# 08_-_MCU.net
KiCad netlist of a schematic drawn in Altium Designer
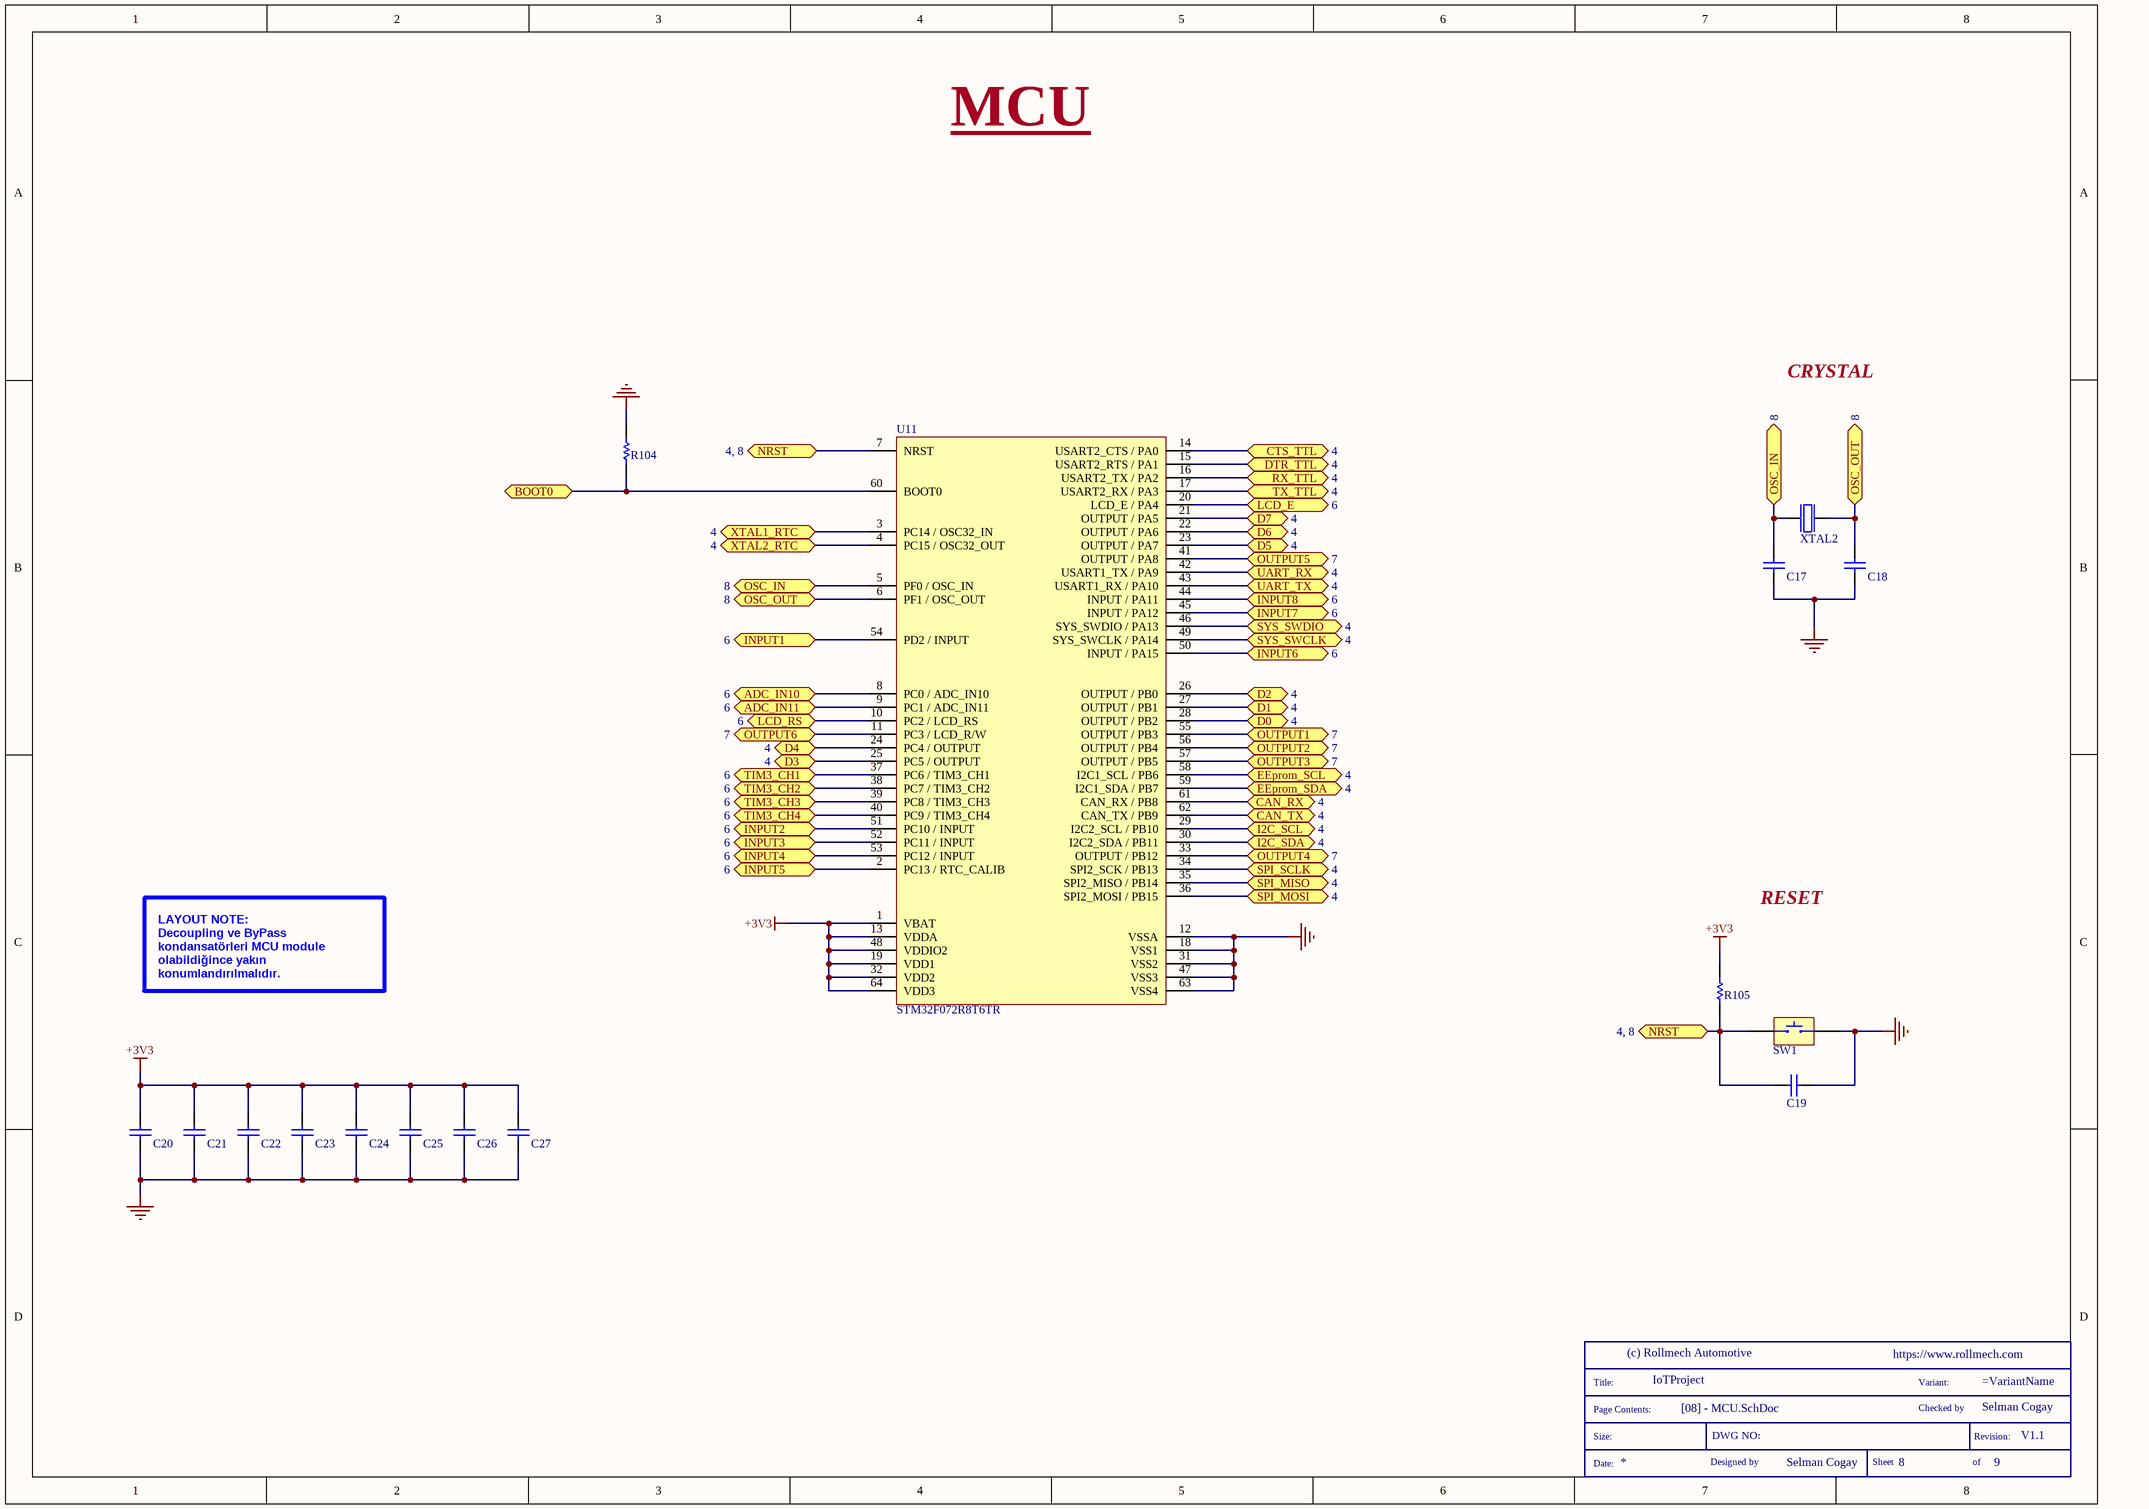
[diagram p0: [08] - MCU.SchDoc]

(export (version "E")
  (design (tool "Eeschema 10.0.6"))
  (components
    (comp (ref "C17")
      (value "22pF 100V")
      (footprint "CAP_CER_0603")
      (description "CAP CER 22PF 100V C0G/NP0 0603")
      (libsource (lib "Rollmech_Altium") (part "GCM1885C2A220FA16D"))
    )
    (comp (ref "C18")
      (value "22pF 100V")
      (footprint "CAP_CER_0603")
      (description "CAP CER 22PF 100V C0G/NP0 0603")
      (libsource (lib "Rollmech_Altium") (part "GCM1885C2A220FA16D"))
    )
    (comp (ref "C19")
      (value "100nF 35V")
      (footprint "CAP_CER_0603")
      (description "CAP CER 100nf 35V X5R 0603")
      (libsource (lib "Rollmech_Altium") (part "GMK107BJ104KAHT"))
    )
    (comp (ref "C20")
      (value "100nF 35V")
      (footprint "CAP_CER_0603")
      (description "CAP CER 100nf 35V X5R 0603")
      (libsource (lib "Rollmech_Altium") (part "GMK107BJ104KAHT"))
    )
    (comp (ref "C21")
      (value "100nF 35V")
      (footprint "CAP_CER_0603")
      (description "CAP CER 100nf 35V X5R 0603")
      (libsource (lib "Rollmech_Altium") (part "GMK107BJ104KAHT"))
    )
    (comp (ref "C22")
      (value "100nF 35V")
      (footprint "CAP_CER_0603")
      (description "CAP CER 100nf 35V X5R 0603")
      (libsource (lib "Rollmech_Altium") (part "GMK107BJ104KAHT"))
    )
    (comp (ref "C23")
      (value "100nF 35V")
      (footprint "CAP_CER_0603")
      (description "CAP CER 100nf 35V X5R 0603")
      (libsource (lib "Rollmech_Altium") (part "GMK107BJ104KAHT"))
    )
    (comp (ref "C24")
      (value "1uF 35V")
      (footprint "C0603")
      (description "CAP CER 1UF 35V")
      (libsource (lib "Rollmech_Altium") (part "CGA3E3X5R1V105K080AB"))
    )
    (comp (ref "C25")
      (value "10nF 100V")
      (footprint "CAP_CER_0805")
      (description "CAP CER 10nF 100V")
      (libsource (lib "Rollmech_Altium") (part "CL21B103KC6WPNC"))
    )
    (comp (ref "C26")
      (value "4.7uF 35V")
      (footprint "CAP_CER_0805")
      (description "CAP CER 100nf 35V X5R 0603")
      (libsource (lib "Rollmech_Altium") (part "GRT21BC8YA475KE13L"))
    )
    (comp (ref "C27")
      (value "4.7uF 35V")
      (footprint "CAP_CER_0805")
      (description "CAP CER 100nf 35V X5R 0603")
      (libsource (lib "Rollmech_Altium") (part "GRT21BC8YA475KE13L"))
    )
    (comp (ref "R104")
      (value "5.6k 1/8W")
      (footprint "RES_0805")
      (description "RES SMD 5.6K OHM 1% 1/8W 0805")
      (libsource (lib "Rollmech_Altium") (part "ERJ-6ENF5601V"))
    )
    (comp (ref "R105")
      (value "5.6k 1/8W")
      (footprint "RES_0805")
      (description "RES SMD 5.6K OHM 1% 1/8W 0805")
      (libsource (lib "Rollmech_Altium") (part "ERJ-6ENF5601V"))
    )
    (comp (ref "SW1")
      (value "TAC SW")
      (footprint "TAC-SW")
      (description "SWITCH TACTILE SPST-NO 0.05A 24V")
      (libsource (lib "Rollmech_Altium") (part "FSMSMTR"))
    )
    (comp (ref "U11")
      (value "STM32F072R8T6TR")
      (footprint "LQFP64")
      (description "IC MCU 32BIT 64KB FLASH 64LQFP")
      (libsource (lib "Rollmech_Altium") (part "STM32F072R8T6TR"))
    )
    (comp (ref "XTAL2")
      (value "8.000MHZ")
      (footprint "XTAL_4SMD")
      (description "CRYSTAL 8.000MHZ")
      (libsource (lib "Rollmech_Altium") (part "ECS-80-18-20BQ-DS"))
    )
  )
  (nets
    (net (code "1") (name "+3V3") (class "Default")
      (node (ref "C20") (pin "2") (pinfunction "2_2") (pintype "passive"))
      (node (ref "C21") (pin "2") (pinfunction "2_2") (pintype "passive"))
      (node (ref "C22") (pin "2") (pinfunction "2_2") (pintype "passive"))
      (node (ref "C23") (pin "2") (pinfunction "2_2") (pintype "passive"))
      (node (ref "C24") (pin "2") (pinfunction "2_2") (pintype "passive"))
      (node (ref "C25") (pin "2") (pinfunction "2_2") (pintype "passive"))
      (node (ref "C26") (pin "2") (pinfunction "2_2") (pintype "passive"))
      (node (ref "C27") (pin "2") (pinfunction "2_2") (pintype "passive"))
      (node (ref "R105") (pin "2") (pinfunction "2_2") (pintype "passive"))
      (node (ref "U11") (pin "1") (pinfunction "VBAT_1") (pintype "passive"))
      (node (ref "U11") (pin "13") (pinfunction "VDDA_13") (pintype "passive"))
      (node (ref "U11") (pin "19") (pinfunction "VDD1_19") (pintype "passive"))
      (node (ref "U11") (pin "32") (pinfunction "VDD2_32") (pintype "passive"))
      (node (ref "U11") (pin "48") (pinfunction "VDDIO2_48") (pintype "passive"))
      (node (ref "U11") (pin "64") (pinfunction "VDD3_64") (pintype "passive"))
    )
    (net (code "2") (name "/ADC_IN10") (class "Default")
      (node (ref "U11") (pin "8") (pinfunction "PC0_/_ADC_IN10_8") (pintype "passive"))
    )
    (net (code "3") (name "/ADC_IN11") (class "Default")
      (node (ref "U11") (pin "9") (pinfunction "PC1_/_ADC_IN11_9") (pintype "passive"))
    )
    (net (code "4") (name "/BOOT0") (class "Default")
      (node (ref "R104") (pin "1") (pinfunction "1_1") (pintype "passive"))
      (node (ref "U11") (pin "60") (pinfunction "BOOT0_60") (pintype "passive"))
    )
    (net (code "5") (name "/CAN_RX") (class "Default")
      (node (ref "U11") (pin "61") (pinfunction "CAN_RX_/_PB8_61") (pintype "passive"))
    )
    (net (code "6") (name "/CAN_TX") (class "Default")
      (node (ref "U11") (pin "62") (pinfunction "CAN_TX_/_PB9_62") (pintype "passive"))
    )
    (net (code "7") (name "/CTS_TTL") (class "Default")
      (node (ref "U11") (pin "14") (pinfunction "USART2_CTS_/_PA0_14") (pintype "passive"))
    )
    (net (code "8") (name "/D0") (class "Default")
      (node (ref "U11") (pin "28") (pinfunction "OUTPUT_/_PB2_28") (pintype "passive"))
    )
    (net (code "9") (name "/D1") (class "Default")
      (node (ref "U11") (pin "27") (pinfunction "OUTPUT_/_PB1_27") (pintype "passive"))
    )
    (net (code "10") (name "/D2") (class "Default")
      (node (ref "U11") (pin "26") (pinfunction "OUTPUT_/_PB0_26") (pintype "passive"))
    )
    (net (code "11") (name "/D3") (class "Default")
      (node (ref "U11") (pin "25") (pinfunction "PC5_/_OUTPUT_25") (pintype "passive"))
    )
    (net (code "12") (name "/D4") (class "Default")
      (node (ref "U11") (pin "24") (pinfunction "PC4_/_OUTPUT_24") (pintype "passive"))
    )
    (net (code "13") (name "/D5") (class "Default")
      (node (ref "U11") (pin "23") (pinfunction "OUTPUT_/_PA7_23") (pintype "passive"))
    )
    (net (code "14") (name "/D6") (class "Default")
      (node (ref "U11") (pin "22") (pinfunction "OUTPUT_/_PA6_22") (pintype "passive"))
    )
    (net (code "15") (name "/D7") (class "Default")
      (node (ref "U11") (pin "21") (pinfunction "OUTPUT_/_PA5_21") (pintype "passive"))
    )
    (net (code "16") (name "/DTR_TTL") (class "Default")
      (node (ref "U11") (pin "15") (pinfunction "USART2_RTS_/_PA1_15") (pintype "passive"))
    )
    (net (code "17") (name "/EEprom_SCL") (class "Default")
      (node (ref "U11") (pin "58") (pinfunction "I2C1_SCL_/_PB6_58") (pintype "passive"))
    )
    (net (code "18") (name "/EEprom_SDA") (class "Default")
      (node (ref "U11") (pin "59") (pinfunction "I2C1_SDA_/_PB7_59") (pintype "passive"))
    )
    (net (code "19") (name "/I2C_SCL") (class "Default")
      (node (ref "U11") (pin "29") (pinfunction "I2C2_SCL_/_PB10_29") (pintype "passive"))
    )
    (net (code "20") (name "/I2C_SDA") (class "Default")
      (node (ref "U11") (pin "30") (pinfunction "I2C2_SDA_/_PB11_30") (pintype "passive"))
    )
    (net (code "21") (name "/INPUT1") (class "Default")
      (node (ref "U11") (pin "54") (pinfunction "PD2_/_INPUT_54") (pintype "passive"))
    )
    (net (code "22") (name "/INPUT2") (class "Default")
      (node (ref "U11") (pin "51") (pinfunction "PC10_/_INPUT_51") (pintype "passive"))
    )
    (net (code "23") (name "/INPUT3") (class "Default")
      (node (ref "U11") (pin "52") (pinfunction "PC11_/_INPUT_52") (pintype "passive"))
    )
    (net (code "24") (name "/INPUT4") (class "Default")
      (node (ref "U11") (pin "53") (pinfunction "PC12_/_INPUT_53") (pintype "passive"))
    )
    (net (code "25") (name "/INPUT5") (class "Default")
      (node (ref "U11") (pin "2") (pinfunction "PC13_/_RTC_CALIB_2") (pintype "passive"))
    )
    (net (code "26") (name "/INPUT6") (class "Default")
      (node (ref "U11") (pin "50") (pinfunction "INPUT_/_PA15_50") (pintype "passive"))
    )
    (net (code "27") (name "/INPUT7") (class "Default")
      (node (ref "U11") (pin "45") (pinfunction "INPUT_/_PA12_45") (pintype "passive"))
    )
    (net (code "28") (name "/INPUT8") (class "Default")
      (node (ref "U11") (pin "44") (pinfunction "INPUT_/_PA11_44") (pintype "passive"))
    )
    (net (code "29") (name "/LCD_E") (class "Default")
      (node (ref "U11") (pin "20") (pinfunction "LCD_E_/_PA4_20") (pintype "passive"))
    )
    (net (code "30") (name "/LCD_RS") (class "Default")
      (node (ref "U11") (pin "10") (pinfunction "PC2_/_LCD_RS_10") (pintype "passive"))
    )
    (net (code "31") (name "/NRST") (class "Default")
      (node (ref "C19") (pin "1") (pinfunction "1_1") (pintype "passive"))
      (node (ref "R105") (pin "1") (pinfunction "1_1") (pintype "passive"))
      (node (ref "SW1") (pin "1") (pinfunction "1_1") (pintype "passive"))
      (node (ref "U11") (pin "7") (pinfunction "NRST_7") (pintype "passive"))
    )
    (net (code "32") (name "/OSC_IN") (class "Default")
      (node (ref "C17") (pin "2") (pinfunction "2_2") (pintype "passive"))
      (node (ref "U11") (pin "5") (pinfunction "PF0_/_OSC_IN_5") (pintype "passive"))
      (node (ref "XTAL2") (pin "3") (pinfunction "3_3") (pintype "passive"))
    )
    (net (code "33") (name "/OSC_OUT") (class "Default")
      (node (ref "C18") (pin "2") (pinfunction "2_2") (pintype "passive"))
      (node (ref "U11") (pin "6") (pinfunction "PF1_/_OSC_OUT_6") (pintype "passive"))
      (node (ref "XTAL2") (pin "1") (pinfunction "1_1") (pintype "passive"))
    )
    (net (code "34") (name "/OUTPUT1") (class "Default")
      (node (ref "U11") (pin "55") (pinfunction "OUTPUT_/_PB3_55") (pintype "passive"))
    )
    (net (code "35") (name "/OUTPUT2") (class "Default")
      (node (ref "U11") (pin "56") (pinfunction "OUTPUT_/_PB4_56") (pintype "passive"))
    )
    (net (code "36") (name "/OUTPUT3") (class "Default")
      (node (ref "U11") (pin "57") (pinfunction "OUTPUT_/_PB5_57") (pintype "passive"))
    )
    (net (code "37") (name "/OUTPUT4") (class "Default")
      (node (ref "U11") (pin "33") (pinfunction "OUTPUT_/_PB12_33") (pintype "passive"))
    )
    (net (code "38") (name "/OUTPUT5") (class "Default")
      (node (ref "U11") (pin "41") (pinfunction "OUTPUT_/_PA8_41") (pintype "passive"))
    )
    (net (code "39") (name "/OUTPUT6") (class "Default")
      (node (ref "U11") (pin "11") (pinfunction "PC3_/_LCD_R/W_11") (pintype "passive"))
    )
    (net (code "40") (name "/RX_TTL") (class "Default")
      (node (ref "U11") (pin "16") (pinfunction "USART2_TX_/_PA2_16") (pintype "passive"))
    )
    (net (code "41") (name "/SPI_MISO") (class "Default")
      (node (ref "U11") (pin "35") (pinfunction "SPI2_MISO_/_PB14_35") (pintype "passive"))
    )
    (net (code "42") (name "/SPI_MOSI") (class "Default")
      (node (ref "U11") (pin "36") (pinfunction "SPI2_MOSI_/_PB15_36") (pintype "passive"))
    )
    (net (code "43") (name "/SPI_SCLK") (class "Default")
      (node (ref "U11") (pin "34") (pinfunction "SPI2_SCK_/_PB13_34") (pintype "passive"))
    )
    (net (code "44") (name "/SYS_SWCLK") (class "Default")
      (node (ref "U11") (pin "49") (pinfunction "SYS_SWCLK_/_PA14_49") (pintype "passive"))
    )
    (net (code "45") (name "/SYS_SWDIO") (class "Default")
      (node (ref "U11") (pin "46") (pinfunction "SYS_SWDIO_/_PA13_46") (pintype "passive"))
    )
    (net (code "46") (name "/TIM3_CH1") (class "Default")
      (node (ref "U11") (pin "37") (pinfunction "PC6_/_TIM3_CH1_37") (pintype "passive"))
    )
    (net (code "47") (name "/TIM3_CH2") (class "Default")
      (node (ref "U11") (pin "38") (pinfunction "PC7_/_TIM3_CH2_38") (pintype "passive"))
    )
    (net (code "48") (name "/TIM3_CH3") (class "Default")
      (node (ref "U11") (pin "39") (pinfunction "PC8_/_TIM3_CH3_39") (pintype "passive"))
    )
    (net (code "49") (name "/TIM3_CH4") (class "Default")
      (node (ref "U11") (pin "40") (pinfunction "PC9_/_TIM3_CH4_40") (pintype "passive"))
    )
    (net (code "50") (name "/TX_TTL") (class "Default")
      (node (ref "U11") (pin "17") (pinfunction "USART2_RX_/_PA3_17") (pintype "passive"))
    )
    (net (code "51") (name "/UART_RX") (class "Default")
      (node (ref "U11") (pin "42") (pinfunction "USART1_TX_/_PA9_42") (pintype "passive"))
    )
    (net (code "52") (name "/UART_TX") (class "Default")
      (node (ref "U11") (pin "43") (pinfunction "USART1_RX_/_PA10_43") (pintype "passive"))
    )
    (net (code "53") (name "/XTAL1_RTC") (class "Default")
      (node (ref "U11") (pin "3") (pinfunction "PC14_/_OSC32_IN_3") (pintype "passive"))
    )
    (net (code "54") (name "/XTAL2_RTC") (class "Default")
      (node (ref "U11") (pin "4") (pinfunction "PC15_/_OSC32_OUT_4") (pintype "passive"))
    )
    (net (code "55") (name "GND") (class "Default")
      (node (ref "C17") (pin "1") (pinfunction "1_1") (pintype "passive"))
      (node (ref "C18") (pin "1") (pinfunction "1_1") (pintype "passive"))
      (node (ref "C19") (pin "2") (pinfunction "2_2") (pintype "passive"))
      (node (ref "C20") (pin "1") (pinfunction "1_1") (pintype "passive"))
      (node (ref "C21") (pin "1") (pinfunction "1_1") (pintype "passive"))
      (node (ref "C22") (pin "1") (pinfunction "1_1") (pintype "passive"))
      (node (ref "C23") (pin "1") (pinfunction "1_1") (pintype "passive"))
      (node (ref "C24") (pin "1") (pinfunction "1_1") (pintype "passive"))
      (node (ref "C25") (pin "1") (pinfunction "1_1") (pintype "passive"))
      (node (ref "C26") (pin "1") (pinfunction "1_1") (pintype "passive"))
      (node (ref "C27") (pin "1") (pinfunction "1_1") (pintype "passive"))
      (node (ref "R104") (pin "2") (pinfunction "2_2") (pintype "passive"))
      (node (ref "SW1") (pin "2") (pinfunction "2_2") (pintype "passive"))
      (node (ref "U11") (pin "12") (pinfunction "VSSA_12") (pintype "passive"))
      (node (ref "U11") (pin "18") (pinfunction "VSS1_18") (pintype "passive"))
      (node (ref "U11") (pin "31") (pinfunction "VSS2_31") (pintype "passive"))
      (node (ref "U11") (pin "47") (pinfunction "VSS3_47") (pintype "passive"))
      (node (ref "U11") (pin "63") (pinfunction "VSS4_63") (pintype "passive"))
    )
  )
)
